# MODULE_SAIL_FLASH.net
KiCad netlist of a schematic drawn in Altium Designer
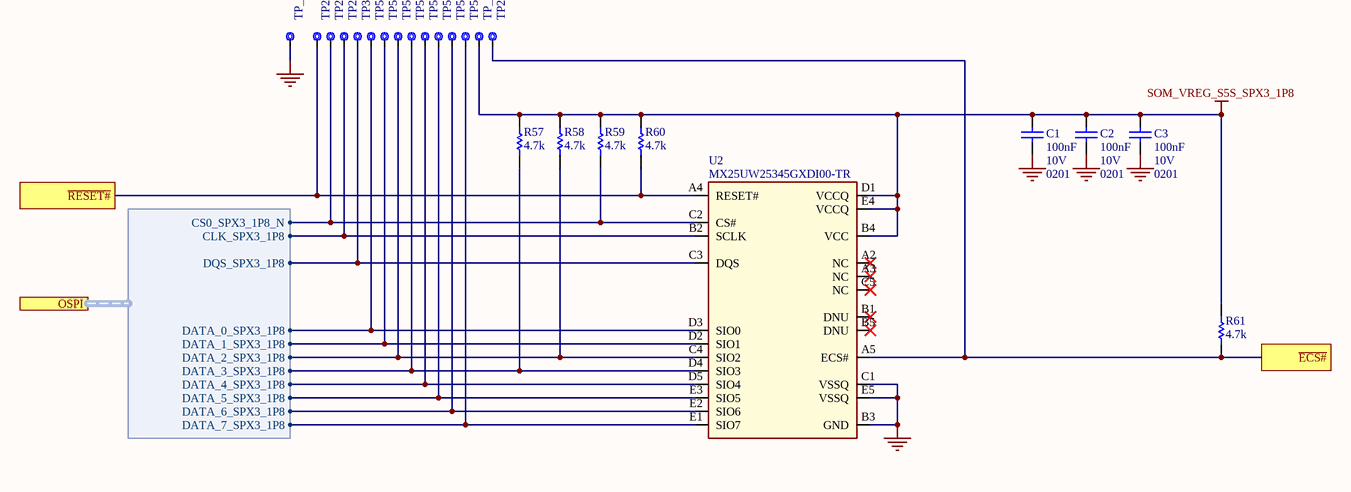
[diagram p0: MODULE_SAIL_FLASH.SchDoc]

(export (version "E")
  (design (tool "Eeschema 10.0.6"))
  (components
    (comp (ref "C1")
      (value "100nF")
      (footprint "CAP-0201")
      (description "CAP CHIP 0201 100nF 10% 10V X5R")
      (fields
        (field (name "PART NUMBER") "CL03A104KP3NNNC")
        (field (name "MANUFACTURER") "Samsung Electro-Mechanics")
        (field (name "VOLTAGE") "10V")
        (field (name "CASE CODE (IMPERIAL)") "0201")
      )
      (libsource (lib "Clean") (part "CAP"))
    )
    (comp (ref "C2")
      (value "100nF")
      (footprint "CAP-0201")
      (description "CAP CHIP 0201 100nF 10% 10V X5R")
      (fields
        (field (name "PART NUMBER") "CL03A104KP3NNNC")
        (field (name "MANUFACTURER") "Samsung Electro-Mechanics")
        (field (name "VOLTAGE") "10V")
        (field (name "CASE CODE (IMPERIAL)") "0201")
      )
      (libsource (lib "Clean") (part "CAP"))
    )
    (comp (ref "C3")
      (value "100nF")
      (footprint "CAP-0201")
      (description "CAP CHIP 0201 100nF 10% 10V X5R")
      (fields
        (field (name "PART NUMBER") "CL03A104KP3NNNC")
        (field (name "MANUFACTURER") "Samsung Electro-Mechanics")
        (field (name "VOLTAGE") "10V")
        (field (name "CASE CODE (IMPERIAL)") "0201")
      )
      (libsource (lib "Clean") (part "CAP"))
    )
    (comp (ref "R57")
      (value "4.7k")
      (footprint "RES-0201")
      (description "RES CHIP 0201 4k7 1% 1/20W")
      (fields (field (name "POWER") "50mW") (field (name "PART NUMBER") "RC0201FR-074K7L"))
      (libsource (lib "Clean") (part "RES"))
    )
    (comp (ref "R58")
      (value "4.7k")
      (footprint "RES-0201")
      (description "RES CHIP 0201 4k7 1% 1/20W")
      (fields (field (name "POWER") "50mW") (field (name "PART NUMBER") "RC0201FR-074K7L"))
      (libsource (lib "Clean") (part "RES"))
    )
    (comp (ref "R59")
      (value "4.7k")
      (footprint "RES-0201")
      (description "RES CHIP 0201 4k7 1% 1/20W")
      (fields (field (name "POWER") "50mW") (field (name "PART NUMBER") "RC0201FR-074K7L"))
      (libsource (lib "Clean") (part "RES"))
    )
    (comp (ref "R60")
      (value "4.7k")
      (footprint "RES-0201")
      (description "RES CHIP 0201 4k7 1% 1/20W")
      (fields (field (name "POWER") "50mW") (field (name "PART NUMBER") "RC0201FR-074K7L"))
      (libsource (lib "Clean") (part "RES"))
    )
    (comp (ref "R61")
      (value "4.7k")
      (footprint "RES-0201")
      (description "RES CHIP 0201 4k7 1% 1/20W")
      (fields (field (name "POWER") "50mW") (field (name "PART NUMBER") "RC0201FR-074K7L"))
      (libsource (lib "Clean") (part "RES"))
    )
    (comp (ref "TP25")
      (value "Test point 1.00mm")
      (footprint "TP-1.00MM")
      (fields (field (name "PART NUMBER") "This is not a component"))
      (libsource (lib "Clean") (part "TESTPOINT"))
    )
    (comp (ref "TP26")
      (value "Test point 1.00mm")
      (footprint "TP-1.00MM")
      (fields (field (name "PART NUMBER") "This is not a component"))
      (libsource (lib "Clean") (part "TESTPOINT"))
    )
    (comp (ref "TP27")
      (value "Test point 1.00mm")
      (footprint "TP-1.00MM")
      (fields (field (name "PART NUMBER") "This is not a component"))
      (libsource (lib "Clean") (part "TESTPOINT"))
    )
    (comp (ref "TP28")
      (value "Test point 1.00mm")
      (footprint "TP-1.00MM")
      (fields (field (name "PART NUMBER") "This is not a component"))
      (libsource (lib "Clean") (part "TESTPOINT"))
    )
    (comp (ref "TP31")
      (value "Test point 1.00mm")
      (footprint "TP-1.00MM")
      (fields (field (name "PART NUMBER") "This is not a component"))
      (libsource (lib "Clean") (part "TESTPOINT"))
    )
    (comp (ref "TP50")
      (value "Test point 1.00mm")
      (footprint "TP-1.00MM")
      (fields (field (name "PART NUMBER") "This is not a component"))
      (libsource (lib "Clean") (part "TESTPOINT"))
    )
    (comp (ref "TP51")
      (value "Test point 1.00mm")
      (footprint "TP-1.00MM")
      (fields (field (name "PART NUMBER") "This is not a component"))
      (libsource (lib "Clean") (part "TESTPOINT"))
    )
    (comp (ref "TP52")
      (value "Test point 1.00mm")
      (footprint "TP-1.00MM")
      (fields (field (name "PART NUMBER") "This is not a component"))
      (libsource (lib "Clean") (part "TESTPOINT"))
    )
    (comp (ref "TP53")
      (value "Test point 1.00mm")
      (footprint "TP-1.00MM")
      (fields (field (name "PART NUMBER") "This is not a component"))
      (libsource (lib "Clean") (part "TESTPOINT"))
    )
    (comp (ref "TP54")
      (value "Test point 1.00mm")
      (footprint "TP-1.00MM")
      (fields (field (name "PART NUMBER") "This is not a component"))
      (libsource (lib "Clean") (part "TESTPOINT"))
    )
    (comp (ref "TP55")
      (value "Test point 1.00mm")
      (footprint "TP-1.00MM")
      (fields (field (name "PART NUMBER") "This is not a component"))
      (libsource (lib "Clean") (part "TESTPOINT"))
    )
    (comp (ref "TP56")
      (value "Test point 1.00mm")
      (footprint "TP-1.00MM")
      (fields (field (name "PART NUMBER") "This is not a component"))
      (libsource (lib "Clean") (part "TESTPOINT"))
    )
    (comp (ref "TP57")
      (value "Test point 1.00mm")
      (footprint "TP-1.00MM")
      (fields (field (name "PART NUMBER") "This is not a component"))
      (libsource (lib "Clean") (part "TESTPOINT"))
    )
    (comp (ref "TP_FLASH_SAIL_1V8")
      (value "Test point 1.00mm")
      (footprint "TP-1.00MM")
      (fields (field (name "PART NUMBER") "This is not a component"))
      (libsource (lib "Clean") (part "TESTPOINT"))
    )
    (comp (ref "TP_FLASH_SAIL_GND")
      (value "Test point 1.00mm")
      (footprint "TP-1.00MM")
      (fields (field (name "PART NUMBER") "This is not a component"))
      (libsource (lib "Clean") (part "TESTPOINT"))
    )
    (comp (ref "U2")
      (value "MX25UW25345GXDI00-TR")
      (footprint "MX25UW25345GXDI00-TR")
      (description "IC NOR FLASH, VDD 1.8V, OSPI, 256Mb x1/x8, BGA24 6x8mm")
      (fields (field (name "MANUFACTURER") "Macronix"))
      (libsource (lib "Clean") (part "MX25UW25345GXDI00-TR-Symbol-1"))
    )
  )
  (nets
    (net (code "3") (name "/~{ECS#}") (class "Default")
      (node (ref "R61") (pin "1") (pinfunction "1_1") (pintype "passive"))
      (node (ref "TP25") (pin "X") (pinfunction "X_X") (pintype "passive"))
      (node (ref "U2") (pin "A5") (pinfunction "ECS#_A5") (pintype "passive"))
    )
    (net (code "4") (name "/~{RESET#}") (class "Default")
      (node (ref "R60") (pin "1") (pinfunction "1_1") (pintype "passive"))
      (node (ref "TP26") (pin "X") (pinfunction "X_X") (pintype "passive"))
      (node (ref "U2") (pin "A4") (pinfunction "RESET#_A4") (pintype "passive"))
    )
    (net (code "5") (name "GND") (class "Default")
      (node (ref "C1") (pin "1") (pinfunction "1_1") (pintype "passive"))
      (node (ref "C2") (pin "1") (pinfunction "1_1") (pintype "passive"))
      (node (ref "C3") (pin "1") (pinfunction "1_1") (pintype "passive"))
      (node (ref "TP_FLASH_SAIL_GND") (pin "X") (pinfunction "X_X") (pintype "passive"))
      (node (ref "U2") (pin "B3") (pinfunction "GND_B3") (pintype "passive"))
      (node (ref "U2") (pin "C1") (pinfunction "VSSQ_C1") (pintype "passive"))
      (node (ref "U2") (pin "E5") (pinfunction "VSSQ_E5") (pintype "passive"))
    )
    (net (code "6") (name "Net-(U2-CS#)") (class "Default")
      (node (ref "R59") (pin "1") (pinfunction "1_1") (pintype "passive"))
      (node (ref "TP27") (pin "X") (pinfunction "X_X") (pintype "passive"))
      (node (ref "U2") (pin "C2") (pinfunction "CS#_C2") (pintype "passive"))
    )
    (net (code "7") (name "Net-(U2-DQS)") (class "Default")
      (node (ref "TP31") (pin "X") (pinfunction "X_X") (pintype "passive"))
      (node (ref "U2") (pin "C3") (pinfunction "DQS_C3") (pintype "passive"))
    )
    (net (code "8") (name "Net-(U2-SCLK)") (class "Default")
      (node (ref "TP28") (pin "X") (pinfunction "X_X") (pintype "passive"))
      (node (ref "U2") (pin "B2") (pinfunction "SCLK_B2") (pintype "passive"))
    )
    (net (code "9") (name "Net-(U2-SIO0)") (class "Default")
      (node (ref "TP50") (pin "X") (pinfunction "X_X") (pintype "passive"))
      (node (ref "U2") (pin "D3") (pinfunction "SIO0_D3") (pintype "passive"))
    )
    (net (code "10") (name "Net-(U2-SIO1)") (class "Default")
      (node (ref "TP51") (pin "X") (pinfunction "X_X") (pintype "passive"))
      (node (ref "U2") (pin "D2") (pinfunction "SIO1_D2") (pintype "passive"))
    )
    (net (code "11") (name "Net-(U2-SIO2)") (class "Default")
      (node (ref "R58") (pin "1") (pinfunction "1_1") (pintype "passive"))
      (node (ref "TP52") (pin "X") (pinfunction "X_X") (pintype "passive"))
      (node (ref "U2") (pin "C4") (pinfunction "SIO2_C4") (pintype "passive"))
    )
    (net (code "12") (name "Net-(U2-SIO3)") (class "Default")
      (node (ref "R57") (pin "1") (pinfunction "1_1") (pintype "passive"))
      (node (ref "TP53") (pin "X") (pinfunction "X_X") (pintype "passive"))
      (node (ref "U2") (pin "D4") (pinfunction "SIO3_D4") (pintype "passive"))
    )
    (net (code "13") (name "Net-(U2-SIO4)") (class "Default")
      (node (ref "TP54") (pin "X") (pinfunction "X_X") (pintype "passive"))
      (node (ref "U2") (pin "D5") (pinfunction "SIO4_D5") (pintype "passive"))
    )
    (net (code "14") (name "Net-(U2-SIO5)") (class "Default")
      (node (ref "TP55") (pin "X") (pinfunction "X_X") (pintype "passive"))
      (node (ref "U2") (pin "E3") (pinfunction "SIO5_E3") (pintype "passive"))
    )
    (net (code "15") (name "Net-(U2-SIO6)") (class "Default")
      (node (ref "TP56") (pin "X") (pinfunction "X_X") (pintype "passive"))
      (node (ref "U2") (pin "E2") (pinfunction "SIO6_E2") (pintype "passive"))
    )
    (net (code "16") (name "Net-(U2-SIO7)") (class "Default")
      (node (ref "TP57") (pin "X") (pinfunction "X_X") (pintype "passive"))
      (node (ref "U2") (pin "E1") (pinfunction "SIO7_E1") (pintype "passive"))
    )
    (net (code "17") (name "SOM_VREG_S5S_SPX3_1P8") (class "Default")
      (node (ref "C1") (pin "2") (pinfunction "2_2") (pintype "passive"))
      (node (ref "C2") (pin "2") (pinfunction "2_2") (pintype "passive"))
      (node (ref "C3") (pin "2") (pinfunction "2_2") (pintype "passive"))
      (node (ref "R57") (pin "2") (pinfunction "2_2") (pintype "passive"))
      (node (ref "R58") (pin "2") (pinfunction "2_2") (pintype "passive"))
      (node (ref "R59") (pin "2") (pinfunction "2_2") (pintype "passive"))
      (node (ref "R60") (pin "2") (pinfunction "2_2") (pintype "passive"))
      (node (ref "R61") (pin "2") (pinfunction "2_2") (pintype "passive"))
      (node (ref "TP_FLASH_SAIL_1V8") (pin "X") (pinfunction "X_X") (pintype "passive"))
      (node (ref "U2") (pin "B4") (pinfunction "VCC_B4") (pintype "passive"))
      (node (ref "U2") (pin "D1") (pinfunction "VCCQ_D1") (pintype "passive"))
      (node (ref "U2") (pin "E4") (pinfunction "VCCQ_E4") (pintype "passive"))
    )
    (net (code "18") (name "unconnected-(U2-DNU-PadB1)") (class "Default")
      (node (ref "U2") (pin "B1") (pinfunction "DNU_B1") (pintype "passive+no_connect"))
    )
    (net (code "19") (name "unconnected-(U2-DNU-PadB5)") (class "Default")
      (node (ref "U2") (pin "B5") (pinfunction "DNU_B5") (pintype "passive+no_connect"))
    )
    (net (code "20") (name "unconnected-(U2-NC-PadA2)") (class "Default")
      (node (ref "U2") (pin "A2") (pinfunction "NC_A2") (pintype "passive+no_connect"))
    )
    (net (code "21") (name "unconnected-(U2-NC-PadA3)") (class "Default")
      (node (ref "U2") (pin "A3") (pinfunction "NC_A3") (pintype "passive+no_connect"))
    )
    (net (code "22") (name "unconnected-(U2-NC-PadC5)") (class "Default")
      (node (ref "U2") (pin "C5") (pinfunction "NC_C5") (pintype "passive+no_connect"))
    )
  )
)
